# Sheet1.net
KiCad netlist of a schematic drawn in Altium Designer
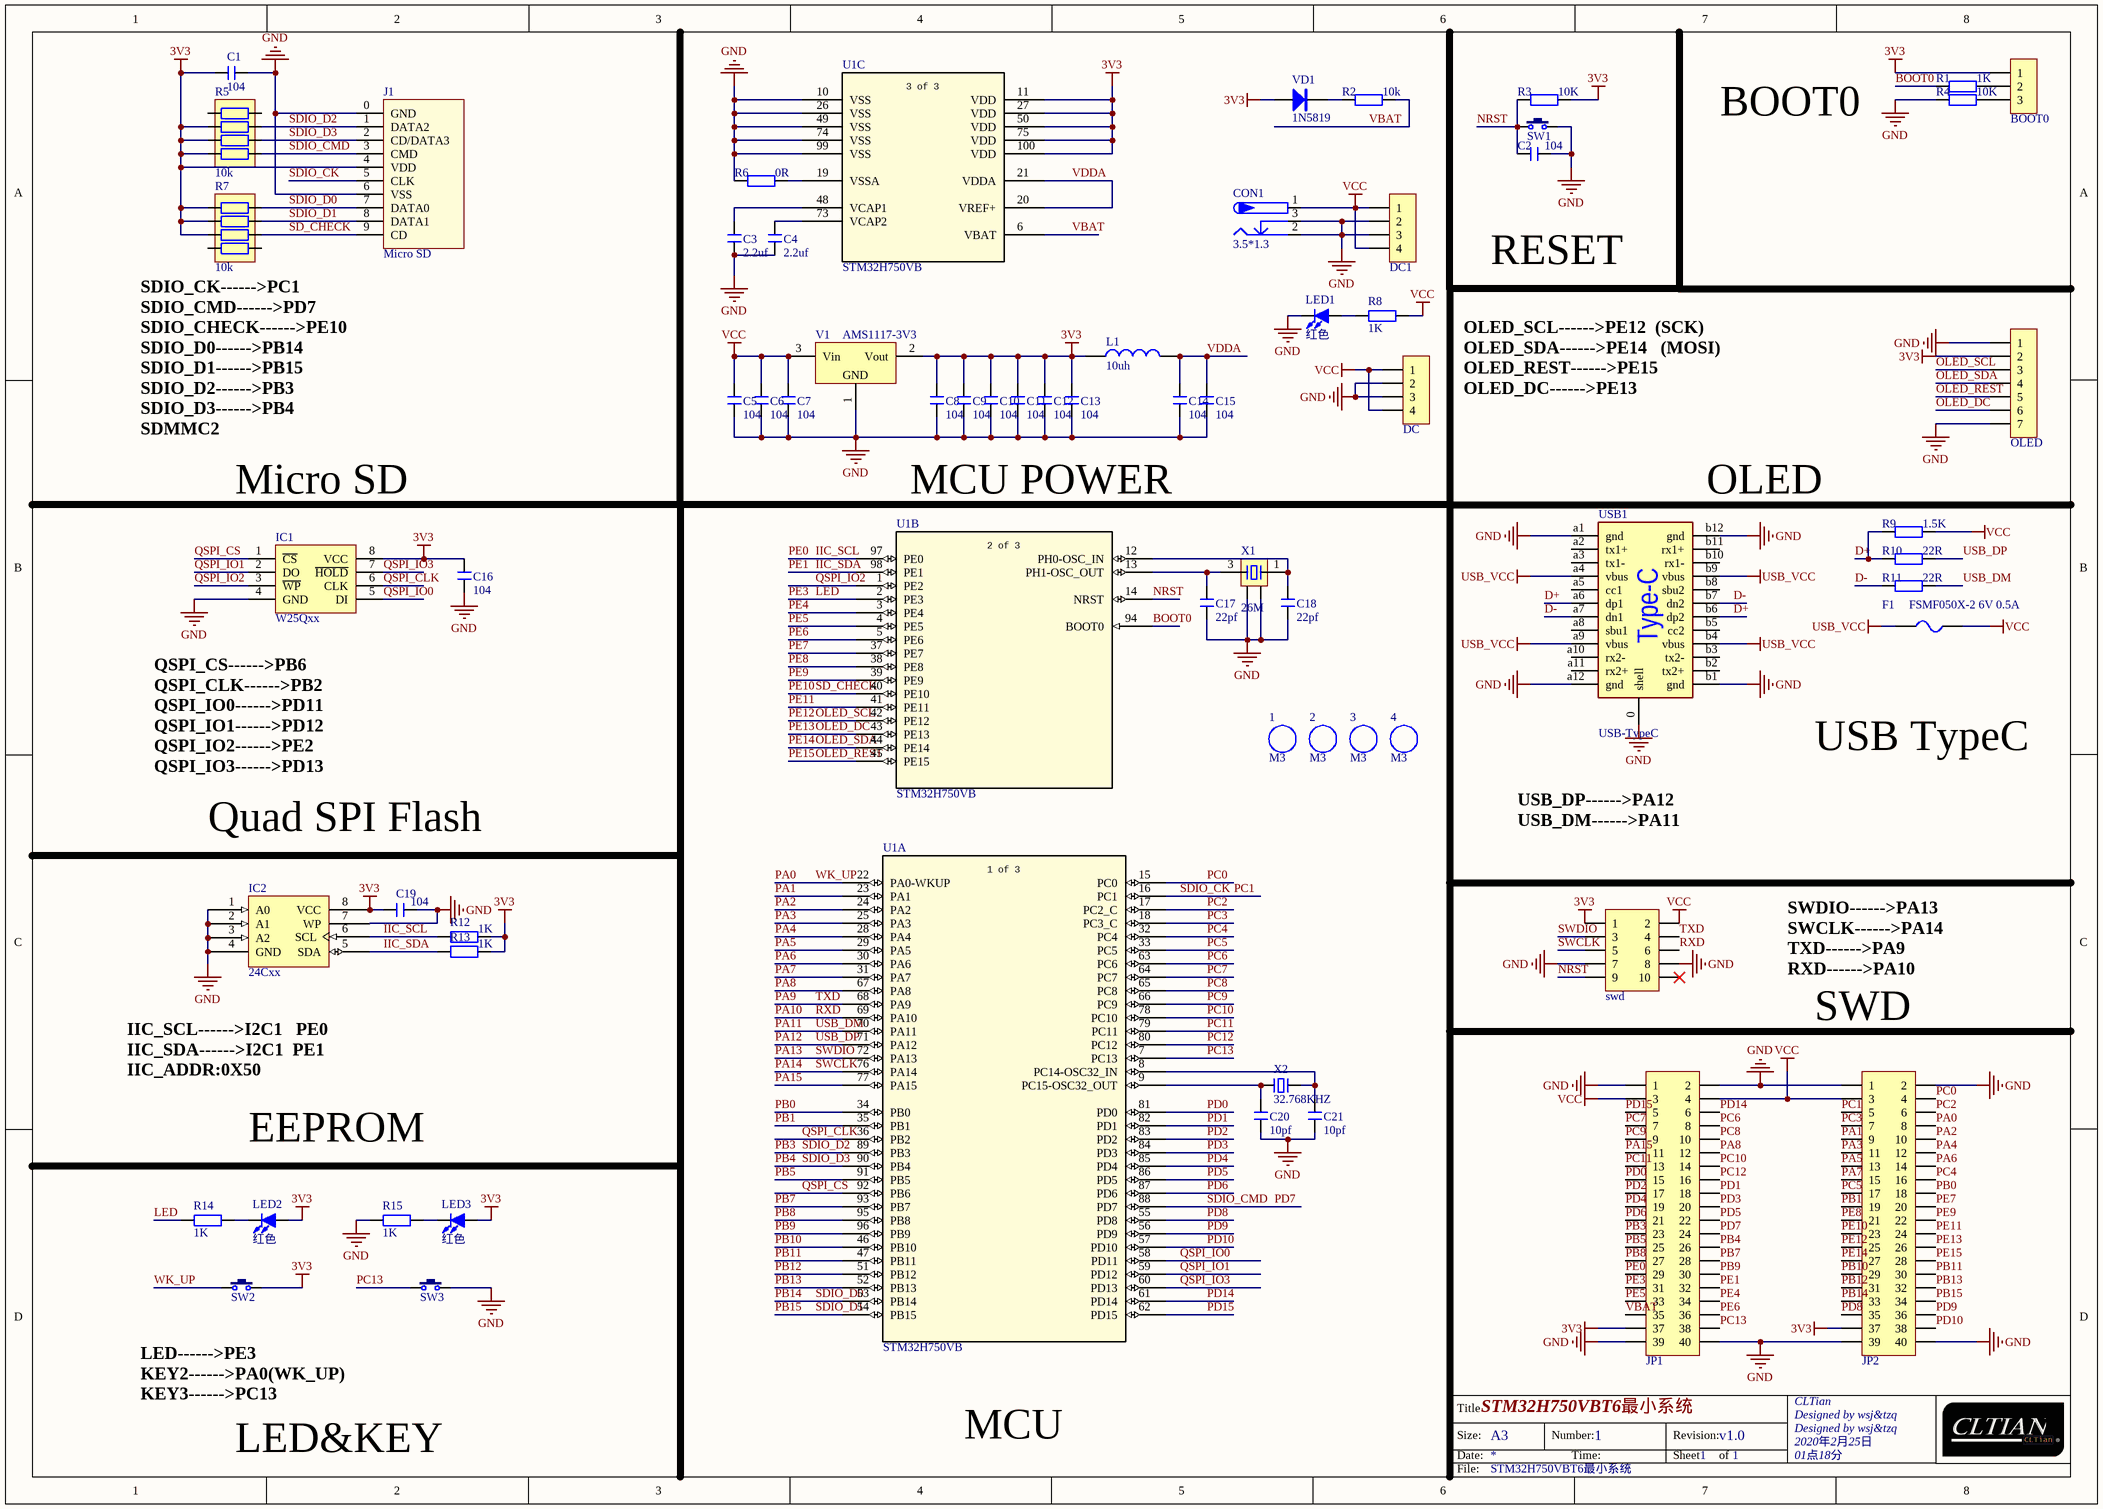
[diagram p0: Sheet1.SchDoc]

(export (version "E")
  (design (tool "Eeschema 10.0.6"))
  (components
    (comp (ref "1")
      (value "M3")
      (footprint "M3 125X200")
      (description "铜柱孔")
      (fields (field (name "版权归属") "黎明电子style"))
      (libsource (lib "未分类器件") (part "M3"))
    )
    (comp (ref "2")
      (value "M3")
      (footprint "M3 125X200")
      (description "铜柱孔")
      (fields (field (name "版权归属") "黎明电子style"))
      (libsource (lib "未分类器件") (part "M3"))
    )
    (comp (ref "3")
      (value "M3")
      (footprint "M3 125X200")
      (description "铜柱孔")
      (fields (field (name "版权归属") "黎明电子style"))
      (libsource (lib "未分类器件") (part "M3"))
    )
    (comp (ref "4")
      (value "M3")
      (footprint "M3 125X200")
      (description "铜柱孔")
      (fields (field (name "版权归属") "黎明电子style"))
      (libsource (lib "未分类器件") (part "M3"))
    )
    (comp (ref "BOOT0")
      (value "HDR-1X3")
      (footprint "HDR-1X3")
      (description "3P接插件")
      (fields (field (name "版权归属") "黎明电子style"))
      (libsource (lib "接插件") (part "Header 3"))
    )
    (comp (ref "C1")
      (value "104")
      (footprint "C 0603")
      (description "无极性贴片电容")
      (fields (field (name "版权归属") "黎明电子style"))
      (libsource (lib "电阻-电容-电感") (part "C"))
    )
    (comp (ref "C2")
      (value "104")
      (footprint "C 0603")
      (description "无极性贴片电容")
      (fields (field (name "版权归属") "黎明电子style"))
      (libsource (lib "电阻-电容-电感") (part "C"))
    )
    (comp (ref "C3")
      (value "2.2uf")
      (footprint "C 0603")
      (description "无极性贴片电容")
      (fields (field (name "版权归属") "黎明电子style"))
      (libsource (lib "电阻-电容-电感") (part "C"))
    )
    (comp (ref "C4")
      (value "2.2uf")
      (footprint "C 0603")
      (description "无极性贴片电容")
      (fields (field (name "版权归属") "黎明电子style"))
      (libsource (lib "电阻-电容-电感") (part "C"))
    )
    (comp (ref "C5")
      (value "104")
      (footprint "C 0603")
      (description "无极性贴片电容")
      (fields (field (name "版权归属") "黎明电子style"))
      (libsource (lib "电阻-电容-电感") (part "C"))
    )
    (comp (ref "C6")
      (value "104")
      (footprint "C 0603")
      (description "无极性贴片电容")
      (fields (field (name "版权归属") "黎明电子style"))
      (libsource (lib "电阻-电容-电感") (part "C"))
    )
    (comp (ref "C7")
      (value "104")
      (footprint "C 0603")
      (description "无极性贴片电容")
      (fields (field (name "版权归属") "黎明电子style"))
      (libsource (lib "电阻-电容-电感") (part "C"))
    )
    (comp (ref "C8")
      (value "104")
      (footprint "C 0603")
      (description "无极性贴片电容")
      (fields (field (name "版权归属") "黎明电子style"))
      (libsource (lib "电阻-电容-电感") (part "C"))
    )
    (comp (ref "C9")
      (value "104")
      (footprint "C 0603")
      (description "无极性贴片电容")
      (fields (field (name "版权归属") "黎明电子style"))
      (libsource (lib "电阻-电容-电感") (part "C"))
    )
    (comp (ref "C10")
      (value "104")
      (footprint "C 0603")
      (description "无极性贴片电容")
      (fields (field (name "版权归属") "黎明电子style"))
      (libsource (lib "电阻-电容-电感") (part "C"))
    )
    (comp (ref "C11")
      (value "104")
      (footprint "C 0603")
      (description "无极性贴片电容")
      (fields (field (name "版权归属") "黎明电子style"))
      (libsource (lib "电阻-电容-电感") (part "C"))
    )
    (comp (ref "C12")
      (value "104")
      (footprint "C 0603")
      (description "无极性贴片电容")
      (fields (field (name "版权归属") "黎明电子style"))
      (libsource (lib "电阻-电容-电感") (part "C"))
    )
    (comp (ref "C13")
      (value "104")
      (footprint "C 0603")
      (description "无极性贴片电容")
      (fields (field (name "版权归属") "黎明电子style"))
      (libsource (lib "电阻-电容-电感") (part "C"))
    )
    (comp (ref "C14")
      (value "104")
      (footprint "C 0603")
      (description "无极性贴片电容")
      (fields (field (name "版权归属") "黎明电子style"))
      (libsource (lib "电阻-电容-电感") (part "C"))
    )
    (comp (ref "C15")
      (value "104")
      (footprint "C 0603")
      (description "无极性贴片电容")
      (fields (field (name "版权归属") "黎明电子style"))
      (libsource (lib "电阻-电容-电感") (part "C"))
    )
    (comp (ref "C16")
      (value "104")
      (footprint "C 0603")
      (description "无极性贴片电容")
      (fields (field (name "版权归属") "黎明电子style"))
      (libsource (lib "电阻-电容-电感") (part "C"))
    )
    (comp (ref "C17")
      (value "22pf")
      (footprint "C 0603")
      (description "无极性贴片电容")
      (fields (field (name "版权归属") "黎明电子style"))
      (libsource (lib "电阻-电容-电感") (part "C"))
    )
    (comp (ref "C18")
      (value "22pf")
      (footprint "C 0603")
      (description "无极性贴片电容")
      (fields (field (name "版权归属") "黎明电子style"))
      (libsource (lib "电阻-电容-电感") (part "C"))
    )
    (comp (ref "C19")
      (value "104")
      (footprint "C 0603")
      (description "无极性贴片电容")
      (fields (field (name "版权归属") "黎明电子style"))
      (libsource (lib "电阻-电容-电感") (part "C"))
    )
    (comp (ref "C20")
      (value "10pf")
      (footprint "C 0603")
      (description "无极性贴片电容")
      (fields (field (name "版权归属") "黎明电子style"))
      (libsource (lib "电阻-电容-电感") (part "C"))
    )
    (comp (ref "C21")
      (value "10pf")
      (footprint "C 0603")
      (description "无极性贴片电容")
      (fields (field (name "版权归属") "黎明电子style"))
      (libsource (lib "电阻-电容-电感") (part "C"))
    )
    (comp (ref "CON1")
      (value "3.5*1.3")
      (footprint "DC-005")
      (description "低压电源接口")
      (fields (field (name "版权归属") "黎明电子style"))
      (libsource (lib "接口类") (part "P-DC"))
    )
    (comp (ref "DC")
      (value "HDR-1X4")
      (footprint "PH2.0 D-W-4P")
      (description "4P接插件")
      (fields (field (name "版权归属") "黎明电子style"))
      (libsource (lib "接插件") (part "Header 4"))
    )
    (comp (ref "DC1")
      (value "HDR-1X4")
      (footprint "PH2.0 D-W-4P")
      (description "4P接插件")
      (fields (field (name "版权归属") "黎明电子style"))
      (libsource (lib "接插件") (part "Header 4"))
    )
    (comp (ref "F1")
      (value "FSMF050X-2 6V 0.5A")
      (footprint "FU 0603")
      (description "贴片保险丝")
      (fields (field (name "版权归属") "黎明电子style"))
      (libsource (lib "保险丝-晶振") (part "FU"))
    )
    (comp (ref "IC1")
      (value "W25Qxx")
      (footprint "SOP8W_N")
      (description "外置Flash")
      (fields (field (name "版权归属") "黎明电子style"))
      (libsource (lib "IC芯片") (part "W25Qxx"))
    )
    (comp (ref "IC2")
      (value "24Cxx")
      (footprint "SOP8_L")
      (description "外置EEPROM")
      (fields (field (name "版权归属") "源创客"))
      (libsource (lib "IC芯片") (part "24Cxx"))
    )
    (comp (ref "J1")
      (value "Micro SD")
      (footprint "Micro SD")
      (description "Micro SD卡")
      (fields (field (name "版权归属") "黎明电子style"))
      (libsource (lib "接口类") (part "Micro SD"))
    )
    (comp (ref "JP1")
      (value "Header 2X11")
      (footprint "HDR-20X2")
      (description "20*2P接插件")
      (fields (field (name "版权归属") "黎明电子style"))
      (libsource (lib "接插件") (part "Header 20X2"))
    )
    (comp (ref "JP2")
      (value "Header 2X11")
      (footprint "HDR-20X2")
      (description "20*2P接插件")
      (fields (field (name "版权归属") "黎明电子style"))
      (libsource (lib "接插件") (part "Header 20X2"))
    )
    (comp (ref "L1")
      (value "10uh")
      (footprint "L 0603")
      (description "小功率贴片电感")
      (fields (field (name "版权归属") "黎明电子style"))
      (libsource (lib "电阻-电容-电感") (part "L"))
    )
    (comp (ref "LED1")
      (value "红色")
      (footprint "LED 0805G")
      (description "贴片LED")
      (fields (field (name "版权归属") "黎明电子style"))
      (libsource (lib "LED") (part "LED-SMD"))
    )
    (comp (ref "LED2")
      (value "红色")
      (footprint "LED 0603B")
      (description "贴片LED")
      (fields (field (name "版权归属") "黎明电子style"))
      (libsource (lib "LED") (part "LED-SMD"))
    )
    (comp (ref "LED3")
      (value "红色")
      (footprint "LED 0603B")
      (description "贴片LED")
      (fields (field (name "版权归属") "黎明电子style"))
      (libsource (lib "LED") (part "LED-SMD"))
    )
    (comp (ref "OLED")
      (value "HDR-1X7")
      (footprint "HDR-1X7")
      (description "7P接插件")
      (fields (field (name "版权归属") "黎明电子style"))
      (libsource (lib "接插件") (part "Header 7"))
    )
    (comp (ref "R1")
      (value "1K")
      (footprint "R 0603-HP")
      (description "贴片电阻")
      (fields (field (name "版权归属") "黎明电子style"))
      (libsource (lib "电阻-电容-电感") (part "R"))
    )
    (comp (ref "R2")
      (value "10k")
      (footprint "R 0603-HP")
      (description "贴片电阻")
      (fields (field (name "版权归属") "黎明电子style"))
      (libsource (lib "电阻-电容-电感") (part "R"))
    )
    (comp (ref "R3")
      (value "10K")
      (footprint "R 0603-HP")
      (description "贴片电阻")
      (fields (field (name "版权归属") "黎明电子style"))
      (libsource (lib "电阻-电容-电感") (part "R"))
    )
    (comp (ref "R4")
      (value "10K")
      (footprint "R 0603-HP")
      (description "贴片电阻")
      (fields (field (name "版权归属") "黎明电子style"))
      (libsource (lib "电阻-电容-电感") (part "R"))
    )
    (comp (ref "R5")
      (value "10k")
      (footprint "RCA-8P4R-0402")
      (description "贴片网络排阻")
      (fields (field (name "版权归属") "黎明电子style"))
      (libsource (lib "电阻-电容-电感") (part "R-8P4R"))
    )
    (comp (ref "R6")
      (value "0R")
      (footprint "R 0603-HP")
      (description "贴片电阻")
      (fields (field (name "版权归属") "黎明电子style"))
      (libsource (lib "电阻-电容-电感") (part "R"))
    )
    (comp (ref "R7")
      (value "10k")
      (footprint "RCA-8P4R-0402")
      (description "贴片网络排阻")
      (fields (field (name "版权归属") "黎明电子style"))
      (libsource (lib "电阻-电容-电感") (part "R-8P4R"))
    )
    (comp (ref "R8")
      (value "1K")
      (footprint "R 0805")
      (description "贴片电阻")
      (fields (field (name "版权归属") "黎明电子style"))
      (libsource (lib "电阻-电容-电感") (part "R"))
    )
    (comp (ref "R9")
      (value "1.5K")
      (footprint "R 0603-HP")
      (description "贴片电阻")
      (fields (field (name "版权归属") "黎明电子style"))
      (libsource (lib "电阻-电容-电感") (part "R"))
    )
    (comp (ref "R10")
      (value "22R")
      (footprint "R 0603-HP")
      (description "贴片电阻")
      (fields (field (name "版权归属") "黎明电子style"))
      (libsource (lib "电阻-电容-电感") (part "R"))
    )
    (comp (ref "R11")
      (value "22R")
      (footprint "R 0603-HP")
      (description "贴片电阻")
      (fields (field (name "版权归属") "黎明电子style"))
      (libsource (lib "电阻-电容-电感") (part "R"))
    )
    (comp (ref "R12")
      (value "1K")
      (footprint "R 0603-HP")
      (description "贴片电阻")
      (fields (field (name "版权归属") "黎明电子style"))
      (libsource (lib "电阻-电容-电感") (part "R"))
    )
    (comp (ref "R13")
      (value "1K")
      (footprint "R 0603-HP")
      (description "贴片电阻")
      (fields (field (name "版权归属") "黎明电子style"))
      (libsource (lib "电阻-电容-电感") (part "R"))
    )
    (comp (ref "R14")
      (value "1K")
      (footprint "R 0603-HP")
      (description "贴片电阻")
      (fields (field (name "版权归属") "黎明电子style"))
      (libsource (lib "电阻-电容-电感") (part "R"))
    )
    (comp (ref "R15")
      (value "1K")
      (footprint "R 0603-HP")
      (description "贴片电阻")
      (fields (field (name "版权归属") "黎明电子style"))
      (libsource (lib "电阻-电容-电感") (part "R"))
    )
    (comp (ref "SW1")
      (value "3x6x5")
      (footprint "TSW SMD-3*6*2.5")
      (description "3x6轻触开关")
      (fields (field (name "版权归属") "黎明电子style"))
      (libsource (lib "按键-开关") (part "TSW 3x6"))
    )
    (comp (ref "SW2")
      (value "3x6x5")
      (footprint "TSW SMD-3*6*2.5")
      (description "3x6轻触开关")
      (fields (field (name "版权归属") "黎明电子style"))
      (libsource (lib "按键-开关") (part "TSW 3x6"))
    )
    (comp (ref "SW3")
      (value "3x6x5")
      (footprint "TSW SMD-3*6*2.5")
      (description "3x6轻触开关")
      (fields (field (name "版权归属") "黎明电子style"))
      (libsource (lib "按键-开关") (part "TSW 3x6"))
    )
    (comp (ref "swd")
      (value "Header 5X2")
      (footprint "HDR-5X2")
      (description "5*2P接插件")
      (fields (field (name "版权归属") "黎明电子style"))
      (libsource (lib "接插件") (part "Header 5X2"))
    )
    (comp (ref "U1")
      (value "STM32H750VB")
      (footprint "LQFP100-14x14mm")
      (description "32位单片机100引脚；")
      (libsource (lib "STM32系列单片机") (part "STM32H750VBTx"))
    )
    (comp (ref "USB1")
      (value "USB-TypeC")
      (footprint "USB_TypeC")
      (description "USB-TypeC型母接口")
      (libsource (lib "接口类") (part "USB_TypeC"))
    )
    (comp (ref "V1")
      (value "AMS1117-3V3")
      (footprint "SOT223_L")
      (description "三端稳压芯片")
      (fields (field (name "版权归属") "黎明电子style"))
      (libsource (lib "IC芯片") (part "AMS1117"))
    )
    (comp (ref "VD1")
      (value "1N5819")
      (footprint "SOD-323")
      (description "高速开关二极管")
      (fields (field (name "版权归属") "黎明电子style"))
      (libsource (lib "二极管-整流桥") (part "1N4148"))
    )
    (comp (ref "X1")
      (value "26M")
      (footprint "XTAL-3225")
      (description "4脚晶振")
      (fields (field (name "版权归属") "黎明电子style"))
      (libsource (lib "保险丝-晶振") (part "XTAL-4"))
    )
    (comp (ref "X2")
      (value "32.768KHZ")
      (footprint "XTAL-3215")
      (description "2脚晶振")
      (fields (field (name "版权归属") "黎明电子style"))
      (libsource (lib "保险丝-晶振") (part "XTAL-2"))
    )
  )
  (nets
    (net (code "1") (name "/BOOT0") (class "Default")
      (node (ref "R1") (pin "1") (pinfunction "1_1") (pintype "passive"))
      (node (ref "U1") (pin "94") (pinfunction "BOOT0_94") (pintype "input"))
    )
    (net (code "2") (name "/D+") (class "Default")
      (node (ref "R10") (pin "1") (pinfunction "1_1") (pintype "passive"))
      (node (ref "R9") (pin "1") (pinfunction "1_1") (pintype "passive"))
      (node (ref "USB1") (pin "a6") (pinfunction "dp1_a6") (pintype "passive"))
      (node (ref "USB1") (pin "b6") (pinfunction "dp2_b6") (pintype "passive"))
    )
    (net (code "3") (name "/D-") (class "Default")
      (node (ref "R11") (pin "1") (pinfunction "1_1") (pintype "passive"))
      (node (ref "USB1") (pin "a7") (pinfunction "dn1_a7") (pintype "passive"))
      (node (ref "USB1") (pin "b7") (pinfunction "dn2_b7") (pintype "passive"))
    )
    (net (code "4") (name "/IIC_SCL") (class "Default")
      (node (ref "IC2") (pin "6") (pinfunction "SCL_6") (pintype "input"))
      (node (ref "JP1") (pin "29") (pinfunction "29_29") (pintype "passive"))
      (node (ref "R12") (pin "1") (pinfunction "1_1") (pintype "passive"))
      (node (ref "U1") (pin "97") (pinfunction "PE0_97") (pintype "bidirectional"))
    )
    (net (code "5") (name "/IIC_SDA") (class "Default")
      (node (ref "IC2") (pin "5") (pinfunction "SDA_5") (pintype "bidirectional"))
      (node (ref "JP1") (pin "32") (pinfunction "32_32") (pintype "passive"))
      (node (ref "R13") (pin "1") (pinfunction "1_1") (pintype "passive"))
      (node (ref "U1") (pin "98") (pinfunction "PE1_98") (pintype "bidirectional"))
    )
    (net (code "6") (name "/LED") (class "Default")
      (node (ref "JP1") (pin "31") (pinfunction "31_31") (pintype "passive"))
      (node (ref "R14") (pin "1") (pinfunction "1_1") (pintype "passive"))
      (node (ref "U1") (pin "2") (pinfunction "PE3_2") (pintype "bidirectional"))
    )
    (net (code "7") (name "/NRST") (class "Default")
      (node (ref "C2") (pin "1") (pinfunction "1_1") (pintype "passive"))
      (node (ref "R3") (pin "2") (pinfunction "2_2") (pintype "passive"))
      (node (ref "SW1") (pin "1") (pinfunction "1_1") (pintype "passive"))
      (node (ref "U1") (pin "14") (pinfunction "NRST_14") (pintype "bidirectional"))
      (node (ref "swd") (pin "9") (pinfunction "9_9") (pintype "passive"))
    )
    (net (code "8") (name "/OLED_DC") (class "Default")
      (node (ref "JP2") (pin "26") (pinfunction "26_26") (pintype "passive"))
      (node (ref "OLED") (pin "6") (pinfunction "6_6") (pintype "passive"))
      (node (ref "U1") (pin "43") (pinfunction "PE13_43") (pintype "bidirectional"))
    )
    (net (code "9") (name "/OLED_REST") (class "Default")
      (node (ref "JP2") (pin "28") (pinfunction "28_28") (pintype "passive"))
      (node (ref "OLED") (pin "5") (pinfunction "5_5") (pintype "passive"))
      (node (ref "U1") (pin "45") (pinfunction "PE15_45") (pintype "bidirectional"))
    )
    (net (code "10") (name "/OLED_SCL") (class "Default")
      (node (ref "JP2") (pin "25") (pinfunction "25_25") (pintype "passive"))
      (node (ref "OLED") (pin "3") (pinfunction "3_3") (pintype "passive"))
      (node (ref "U1") (pin "42") (pinfunction "PE12_42") (pintype "bidirectional"))
    )
    (net (code "11") (name "/OLED_SDA") (class "Default")
      (node (ref "JP2") (pin "27") (pinfunction "27_27") (pintype "passive"))
      (node (ref "OLED") (pin "4") (pinfunction "4_4") (pintype "passive"))
      (node (ref "U1") (pin "44") (pinfunction "PE14_44") (pintype "bidirectional"))
    )
    (net (code "12") (name "/PA0") (class "Default")
      (node (ref "JP2") (pin "8") (pinfunction "8_8") (pintype "passive"))
      (node (ref "SW2") (pin "1") (pinfunction "1_1") (pintype "passive"))
      (node (ref "U1") (pin "22") (pinfunction "PA0-WKUP_22") (pintype "bidirectional"))
    )
    (net (code "13") (name "/PA1") (class "Default")
      (node (ref "JP2") (pin "9") (pinfunction "9_9") (pintype "passive"))
      (node (ref "U1") (pin "23") (pinfunction "PA1_23") (pintype "bidirectional"))
    )
    (net (code "14") (name "/PA2") (class "Default")
      (node (ref "JP2") (pin "10") (pinfunction "10_10") (pintype "passive"))
      (node (ref "U1") (pin "24") (pinfunction "PA2_24") (pintype "bidirectional"))
    )
    (net (code "15") (name "/PA3") (class "Default")
      (node (ref "JP2") (pin "11") (pinfunction "11_11") (pintype "passive"))
      (node (ref "U1") (pin "25") (pinfunction "PA3_25") (pintype "bidirectional"))
    )
    (net (code "16") (name "/PA4") (class "Default")
      (node (ref "JP2") (pin "12") (pinfunction "12_12") (pintype "passive"))
      (node (ref "U1") (pin "28") (pinfunction "PA4_28") (pintype "bidirectional"))
    )
    (net (code "17") (name "/PA5") (class "Default")
      (node (ref "JP2") (pin "13") (pinfunction "13_13") (pintype "passive"))
      (node (ref "U1") (pin "29") (pinfunction "PA5_29") (pintype "bidirectional"))
    )
    (net (code "18") (name "/PA6") (class "Default")
      (node (ref "JP2") (pin "14") (pinfunction "14_14") (pintype "passive"))
      (node (ref "U1") (pin "30") (pinfunction "PA6_30") (pintype "bidirectional"))
    )
    (net (code "19") (name "/PA7") (class "Default")
      (node (ref "JP2") (pin "15") (pinfunction "15_15") (pintype "passive"))
      (node (ref "U1") (pin "31") (pinfunction "PA7_31") (pintype "bidirectional"))
    )
    (net (code "20") (name "/PA8") (class "Default")
      (node (ref "JP1") (pin "12") (pinfunction "12_12") (pintype "passive"))
      (node (ref "U1") (pin "67") (pinfunction "PA8_67") (pintype "bidirectional"))
    )
    (net (code "21") (name "/PA9") (class "Default")
      (node (ref "U1") (pin "68") (pinfunction "PA9_68") (pintype "bidirectional"))
      (node (ref "swd") (pin "4") (pinfunction "4_4") (pintype "passive"))
    )
    (net (code "22") (name "/PA10") (class "Default")
      (node (ref "U1") (pin "69") (pinfunction "PA10_69") (pintype "bidirectional"))
      (node (ref "swd") (pin "6") (pinfunction "6_6") (pintype "passive"))
    )
    (net (code "23") (name "/PA11") (class "Default")
      (node (ref "R11") (pin "2") (pinfunction "2_2") (pintype "passive"))
      (node (ref "U1") (pin "70") (pinfunction "PA11_70") (pintype "bidirectional"))
    )
    (net (code "24") (name "/PA12") (class "Default")
      (node (ref "R10") (pin "2") (pinfunction "2_2") (pintype "passive"))
      (node (ref "U1") (pin "71") (pinfunction "PA12_71") (pintype "bidirectional"))
    )
    (net (code "25") (name "/PA13") (class "Default")
      (node (ref "U1") (pin "72") (pinfunction "PA13_72") (pintype "bidirectional"))
      (node (ref "swd") (pin "3") (pinfunction "3_3") (pintype "passive"))
    )
    (net (code "26") (name "/PA14") (class "Default")
      (node (ref "U1") (pin "76") (pinfunction "PA14_76") (pintype "bidirectional"))
      (node (ref "swd") (pin "5") (pinfunction "5_5") (pintype "passive"))
    )
    (net (code "27") (name "/PA15") (class "Default")
      (node (ref "JP1") (pin "11") (pinfunction "11_11") (pintype "passive"))
      (node (ref "U1") (pin "77") (pinfunction "PA15_77") (pintype "bidirectional"))
    )
    (net (code "28") (name "/PB0") (class "Default")
      (node (ref "JP2") (pin "18") (pinfunction "18_18") (pintype "passive"))
      (node (ref "U1") (pin "34") (pinfunction "PB0_34") (pintype "bidirectional"))
    )
    (net (code "29") (name "/PB1") (class "Default")
      (node (ref "JP2") (pin "19") (pinfunction "19_19") (pintype "passive"))
      (node (ref "U1") (pin "35") (pinfunction "PB1_35") (pintype "bidirectional"))
    )
    (net (code "30") (name "/PB3") (class "Default")
      (node (ref "J1") (pin "1") (pinfunction "DATA2_1") (pintype "passive"))
      (node (ref "JP1") (pin "23") (pinfunction "23_23") (pintype "passive"))
      (node (ref "R5") (pin "7") (pinfunction "7_7") (pintype "passive"))
      (node (ref "U1") (pin "89") (pinfunction "PB3_89") (pintype "bidirectional"))
    )
    (net (code "31") (name "/PB4") (class "Default")
      (node (ref "J1") (pin "2") (pinfunction "CD/DATA3_2") (pintype "passive"))
      (node (ref "JP1") (pin "26") (pinfunction "26_26") (pintype "passive"))
      (node (ref "R5") (pin "6") (pinfunction "6_6") (pintype "passive"))
      (node (ref "U1") (pin "90") (pinfunction "PB4_90") (pintype "bidirectional"))
    )
    (net (code "32") (name "/PB5") (class "Default")
      (node (ref "JP1") (pin "25") (pinfunction "25_25") (pintype "passive"))
      (node (ref "U1") (pin "91") (pinfunction "PB5_91") (pintype "bidirectional"))
    )
    (net (code "33") (name "/PB7") (class "Default")
      (node (ref "JP1") (pin "28") (pinfunction "28_28") (pintype "passive"))
      (node (ref "U1") (pin "93") (pinfunction "PB7_93") (pintype "bidirectional"))
    )
    (net (code "34") (name "/PB8") (class "Default")
      (node (ref "JP1") (pin "27") (pinfunction "27_27") (pintype "passive"))
      (node (ref "U1") (pin "95") (pinfunction "PB8_95") (pintype "bidirectional"))
    )
    (net (code "35") (name "/PB9") (class "Default")
      (node (ref "JP1") (pin "30") (pinfunction "30_30") (pintype "passive"))
      (node (ref "U1") (pin "96") (pinfunction "PB9_96") (pintype "bidirectional"))
    )
    (net (code "36") (name "/PB10") (class "Default")
      (node (ref "JP2") (pin "29") (pinfunction "29_29") (pintype "passive"))
      (node (ref "U1") (pin "46") (pinfunction "PB10_46") (pintype "bidirectional"))
    )
    (net (code "37") (name "/PB11") (class "Default")
      (node (ref "JP2") (pin "30") (pinfunction "30_30") (pintype "passive"))
      (node (ref "U1") (pin "47") (pinfunction "PB11_47") (pintype "bidirectional"))
    )
    (net (code "38") (name "/PB12") (class "Default")
      (node (ref "JP2") (pin "31") (pinfunction "31_31") (pintype "passive"))
      (node (ref "U1") (pin "51") (pinfunction "PB12_51") (pintype "bidirectional"))
    )
    (net (code "39") (name "/PB13") (class "Default")
      (node (ref "JP2") (pin "32") (pinfunction "32_32") (pintype "passive"))
      (node (ref "U1") (pin "52") (pinfunction "PB13_52") (pintype "bidirectional"))
    )
    (net (code "40") (name "/PB14") (class "Default")
      (node (ref "J1") (pin "7") (pinfunction "DATA0_7") (pintype "passive"))
      (node (ref "JP2") (pin "33") (pinfunction "33_33") (pintype "passive"))
      (node (ref "R7") (pin "8") (pinfunction "8_8") (pintype "passive"))
      (node (ref "U1") (pin "53") (pinfunction "PB14_53") (pintype "bidirectional"))
    )
    (net (code "41") (name "/PB15") (class "Default")
      (node (ref "J1") (pin "8") (pinfunction "DATA1_8") (pintype "passive"))
      (node (ref "JP2") (pin "34") (pinfunction "34_34") (pintype "passive"))
      (node (ref "R7") (pin "7") (pinfunction "7_7") (pintype "passive"))
      (node (ref "U1") (pin "54") (pinfunction "PB15_54") (pintype "bidirectional"))
    )
    (net (code "42") (name "/PC0") (class "Default")
      (node (ref "JP2") (pin "4") (pinfunction "4_4") (pintype "passive"))
      (node (ref "U1") (pin "15") (pinfunction "PC0_15") (pintype "bidirectional"))
    )
    (net (code "43") (name "/PC1") (class "Default")
      (node (ref "J1") (pin "5") (pinfunction "CLK_5") (pintype "passive"))
      (node (ref "JP2") (pin "5") (pinfunction "5_5") (pintype "passive"))
      (node (ref "U1") (pin "16") (pinfunction "PC1_16") (pintype "bidirectional"))
    )
    (net (code "44") (name "/PC2") (class "Default")
      (node (ref "JP2") (pin "6") (pinfunction "6_6") (pintype "passive"))
      (node (ref "U1") (pin "17") (pinfunction "PC2_C_17") (pintype "bidirectional"))
    )
    (net (code "45") (name "/PC3") (class "Default")
      (node (ref "JP2") (pin "7") (pinfunction "7_7") (pintype "passive"))
      (node (ref "U1") (pin "18") (pinfunction "PC3_C_18") (pintype "bidirectional"))
    )
    (net (code "46") (name "/PC4") (class "Default")
      (node (ref "JP2") (pin "16") (pinfunction "16_16") (pintype "passive"))
      (node (ref "U1") (pin "32") (pinfunction "PC4_32") (pintype "bidirectional"))
    )
    (net (code "47") (name "/PC5") (class "Default")
      (node (ref "JP2") (pin "17") (pinfunction "17_17") (pintype "passive"))
      (node (ref "U1") (pin "33") (pinfunction "PC5_33") (pintype "bidirectional"))
    )
    (net (code "48") (name "/PC6") (class "Default")
      (node (ref "JP1") (pin "8") (pinfunction "8_8") (pintype "passive"))
      (node (ref "U1") (pin "63") (pinfunction "PC6_63") (pintype "bidirectional"))
    )
    (net (code "49") (name "/PC7") (class "Default")
      (node (ref "JP1") (pin "7") (pinfunction "7_7") (pintype "passive"))
      (node (ref "U1") (pin "64") (pinfunction "PC7_64") (pintype "bidirectional"))
    )
    (net (code "50") (name "/PC8") (class "Default")
      (node (ref "JP1") (pin "10") (pinfunction "10_10") (pintype "passive"))
      (node (ref "U1") (pin "65") (pinfunction "PC8_65") (pintype "bidirectional"))
    )
    (net (code "51") (name "/PC9") (class "Default")
      (node (ref "JP1") (pin "9") (pinfunction "9_9") (pintype "passive"))
      (node (ref "U1") (pin "66") (pinfunction "PC9_66") (pintype "bidirectional"))
    )
    (net (code "52") (name "/PC10") (class "Default")
      (node (ref "JP1") (pin "14") (pinfunction "14_14") (pintype "passive"))
      (node (ref "U1") (pin "78") (pinfunction "PC10_78") (pintype "bidirectional"))
    )
    (net (code "53") (name "/PC11") (class "Default")
      (node (ref "JP1") (pin "13") (pinfunction "13_13") (pintype "passive"))
      (node (ref "U1") (pin "79") (pinfunction "PC11_79") (pintype "bidirectional"))
    )
    (net (code "54") (name "/PC12") (class "Default")
      (node (ref "JP1") (pin "16") (pinfunction "16_16") (pintype "passive"))
      (node (ref "U1") (pin "80") (pinfunction "PC12_80") (pintype "bidirectional"))
    )
    (net (code "55") (name "/PC13") (class "Default")
      (node (ref "JP1") (pin "38") (pinfunction "38_38") (pintype "passive"))
      (node (ref "SW3") (pin "1") (pinfunction "1_1") (pintype "passive"))
      (node (ref "U1") (pin "7") (pinfunction "PC13_7") (pintype "bidirectional"))
    )
    (net (code "56") (name "/PD0") (class "Default")
      (node (ref "JP1") (pin "15") (pinfunction "15_15") (pintype "passive"))
      (node (ref "U1") (pin "81") (pinfunction "PD0_81") (pintype "bidirectional"))
    )
    (net (code "57") (name "/PD1") (class "Default")
      (node (ref "JP1") (pin "18") (pinfunction "18_18") (pintype "passive"))
      (node (ref "U1") (pin "82") (pinfunction "PD1_82") (pintype "bidirectional"))
    )
    (net (code "58") (name "/PD2") (class "Default")
      (node (ref "JP1") (pin "17") (pinfunction "17_17") (pintype "passive"))
      (node (ref "U1") (pin "83") (pinfunction "PD2_83") (pintype "bidirectional"))
    )
    (net (code "59") (name "/PD3") (class "Default")
      (node (ref "JP1") (pin "20") (pinfunction "20_20") (pintype "passive"))
      (node (ref "U1") (pin "84") (pinfunction "PD3_84") (pintype "bidirectional"))
    )
    (net (code "60") (name "/PD4") (class "Default")
      (node (ref "JP1") (pin "19") (pinfunction "19_19") (pintype "passive"))
      (node (ref "U1") (pin "85") (pinfunction "PD4_85") (pintype "bidirectional"))
    )
    (net (code "61") (name "/PD5") (class "Default")
      (node (ref "JP1") (pin "22") (pinfunction "22_22") (pintype "passive"))
      (node (ref "U1") (pin "86") (pinfunction "PD5_86") (pintype "bidirectional"))
    )
    (net (code "62") (name "/PD6") (class "Default")
      (node (ref "JP1") (pin "21") (pinfunction "21_21") (pintype "passive"))
      (node (ref "U1") (pin "87") (pinfunction "PD6_87") (pintype "bidirectional"))
    )
    (net (code "63") (name "/PD7") (class "Default")
      (node (ref "J1") (pin "3") (pinfunction "CMD_3") (pintype "passive"))
      (node (ref "JP1") (pin "24") (pinfunction "24_24") (pintype "passive"))
      (node (ref "R5") (pin "5") (pinfunction "5_5") (pintype "passive"))
      (node (ref "U1") (pin "88") (pinfunction "PD7_88") (pintype "bidirectional"))
    )
    (net (code "64") (name "/PD8") (class "Default")
      (node (ref "JP2") (pin "35") (pinfunction "35_35") (pintype "passive"))
      (node (ref "U1") (pin "55") (pinfunction "PD8_55") (pintype "bidirectional"))
    )
    (net (code "65") (name "/PD9") (class "Default")
      (node (ref "JP2") (pin "36") (pinfunction "36_36") (pintype "passive"))
      (node (ref "U1") (pin "56") (pinfunction "PD9_56") (pintype "bidirectional"))
    )
    (net (code "66") (name "/PD10") (class "Default")
      (node (ref "JP2") (pin "38") (pinfunction "38_38") (pintype "passive"))
      (node (ref "U1") (pin "57") (pinfunction "PD10_57") (pintype "bidirectional"))
    )
    (net (code "67") (name "/PD14") (class "Default")
      (node (ref "JP1") (pin "6") (pinfunction "6_6") (pintype "passive"))
      (node (ref "U1") (pin "61") (pinfunction "PD14_61") (pintype "bidirectional"))
    )
    (net (code "68") (name "/PD15") (class "Default")
      (node (ref "JP1") (pin "5") (pinfunction "5_5") (pintype "passive"))
      (node (ref "U1") (pin "62") (pinfunction "PD15_62") (pintype "bidirectional"))
    )
    (net (code "69") (name "/PE4") (class "Default")
      (node (ref "JP1") (pin "34") (pinfunction "34_34") (pintype "passive"))
      (node (ref "U1") (pin "3") (pinfunction "PE4_3") (pintype "bidirectional"))
    )
    (net (code "70") (name "/PE5") (class "Default")
      (node (ref "JP1") (pin "33") (pinfunction "33_33") (pintype "passive"))
      (node (ref "U1") (pin "4") (pinfunction "PE5_4") (pintype "bidirectional"))
    )
    (net (code "71") (name "/PE6") (class "Default")
      (node (ref "JP1") (pin "36") (pinfunction "36_36") (pintype "passive"))
      (node (ref "U1") (pin "5") (pinfunction "PE6_5") (pintype "bidirectional"))
    )
    (net (code "72") (name "/PE7") (class "Default")
      (node (ref "JP2") (pin "20") (pinfunction "20_20") (pintype "passive"))
      (node (ref "U1") (pin "37") (pinfunction "PE7_37") (pintype "bidirectional"))
    )
    (net (code "73") (name "/PE8") (class "Default")
      (node (ref "JP2") (pin "21") (pinfunction "21_21") (pintype "passive"))
      (node (ref "U1") (pin "38") (pinfunction "PE8_38") (pintype "bidirectional"))
    )
    (net (code "74") (name "/PE9") (class "Default")
      (node (ref "JP2") (pin "22") (pinfunction "22_22") (pintype "passive"))
      (node (ref "U1") (pin "39") (pinfunction "PE9_39") (pintype "bidirectional"))
    )
    (net (code "75") (name "/PE10") (class "Default")
      (node (ref "J1") (pin "9") (pinfunction "CD_9") (pintype "passive"))
      (node (ref "JP2") (pin "23") (pinfunction "23_23") (pintype "passive"))
      (node (ref "R7") (pin "6") (pinfunction "6_6") (pintype "passive"))
      (node (ref "U1") (pin "40") (pinfunction "PE10_40") (pintype "bidirectional"))
    )
    (net (code "76") (name "/PE11") (class "Default")
      (node (ref "JP2") (pin "24") (pinfunction "24_24") (pintype "passive"))
      (node (ref "U1") (pin "41") (pinfunction "PE11_41") (pintype "bidirectional"))
    )
    (net (code "77") (name "/QSPI_CLK") (class "Default")
      (node (ref "IC1") (pin "6") (pinfunction "CLK_6") (pintype "passive"))
      (node (ref "U1") (pin "36") (pinfunction "PB2_36") (pintype "bidirectional"))
    )
    (net (code "78") (name "/QSPI_CS") (class "Default")
      (node (ref "IC1") (pin "1") (pinfunction "~{CS}_1") (pintype "passive"))
      (node (ref "U1") (pin "92") (pinfunction "PB6_92") (pintype "bidirectional"))
    )
    (net (code "79") (name "/QSPI_IO0") (class "Default")
      (node (ref "IC1") (pin "5") (pinfunction "DI_5") (pintype "passive"))
      (node (ref "U1") (pin "58") (pinfunction "PD11_58") (pintype "bidirectional"))
    )
    (net (code "80") (name "/QSPI_IO1") (class "Default")
      (node (ref "IC1") (pin "2") (pinfunction "DO_2") (pintype "passive"))
      (node (ref "U1") (pin "59") (pinfunction "PD12_59") (pintype "bidirectional"))
    )
    (net (code "81") (name "/QSPI_IO2") (class "Default")
      (node (ref "IC1") (pin "3") (pinfunction "~{WP}_3") (pintype "passive"))
      (node (ref "U1") (pin "1") (pinfunction "PE2_1") (pintype "bidirectional"))
    )
    (net (code "82") (name "/QSPI_IO3") (class "Default")
      (node (ref "IC1") (pin "7") (pinfunction "~{HOLD}_7") (pintype "passive"))
      (node (ref "U1") (pin "60") (pinfunction "PD13_60") (pintype "bidirectional"))
    )
    (net (code "83") (name "/VBAT") (class "Default")
      (node (ref "JP1") (pin "35") (pinfunction "35_35") (pintype "passive"))
      (node (ref "R2") (pin "1") (pinfunction "1_1") (pintype "passive"))
      (node (ref "U1") (pin "6") (pinfunction "VBAT_6") (pintype "power_in"))
    )
    (net (code "84") (name "/VDDA") (class "Default")
      (node (ref "C14") (pin "2") (pinfunction "2_2") (pintype "passive"))
      (node (ref "C15") (pin "2") (pinfunction "2_2") (pintype "passive"))
      (node (ref "L1") (pin "2") (pinfunction "2_2") (pintype "passive"))
      (node (ref "U1") (pin "20") (pinfunction "VREF+_20") (pintype "power_in"))
      (node (ref "U1") (pin "21") (pinfunction "VDDA_21") (pintype "power_in"))
    )
    (net (code "85") (name "3V3") (class "Default")
      (node (ref "BOOT0") (pin "1") (pinfunction "1_1") (pintype "passive"))
      (node (ref "C1") (pin "2") (pinfunction "2_2") (pintype "passive"))
      (node (ref "C10") (pin "2") (pinfunction "2_2") (pintype "passive"))
      (node (ref "C11") (pin "2") (pinfunction "2_2") (pintype "passive"))
      (node (ref "C12") (pin "2") (pinfunction "2_2") (pintype "passive"))
      (node (ref "C13") (pin "2") (pinfunction "2_2") (pintype "passive"))
      (node (ref "C16") (pin "2") (pinfunction "2_2") (pintype "passive"))
      (node (ref "C19") (pin "2") (pinfunction "2_2") (pintype "passive"))
      (node (ref "C8") (pin "2") (pinfunction "2_2") (pintype "passive"))
      (node (ref "C9") (pin "2") (pinfunction "2_2") (pintype "passive"))
      (node (ref "IC1") (pin "8") (pinfunction "VCC_8") (pintype "passive"))
      (node (ref "IC2") (pin "8") (pinfunction "VCC_8") (pintype "power_in"))
      (node (ref "J1") (pin "4") (pinfunction "VDD_4") (pintype "passive"))
      (node (ref "JP1") (pin "37") (pinfunction "37_37") (pintype "passive"))
      (node (ref "JP2") (pin "37") (pinfunction "37_37") (pintype "passive"))
      (node (ref "L1") (pin "1") (pinfunction "1_1") (pintype "passive"))
      (node (ref "LED2") (pin "1") (pinfunction "A_1") (pintype "passive"))
      (node (ref "LED3") (pin "1") (pinfunction "A_1") (pintype "passive"))
      (node (ref "OLED") (pin "2") (pinfunction "2_2") (pintype "passive"))
      (node (ref "R12") (pin "2") (pinfunction "2_2") (pintype "passive"))
      (node (ref "R13") (pin "2") (pinfunction "2_2") (pintype "passive"))
      (node (ref "R3") (pin "1") (pinfunction "1_1") (pintype "passive"))
      (node (ref "R5") (pin "2") (pinfunction "2_2") (pintype "passive"))
      (node (ref "R5") (pin "3") (pinfunction "3_3") (pintype "passive"))
      (node (ref "R5") (pin "4") (pinfunction "4_4") (pintype "passive"))
      (node (ref "R7") (pin "1") (pinfunction "1_1") (pintype "passive"))
      (node (ref "R7") (pin "2") (pinfunction "2_2") (pintype "passive"))
      (node (ref "R7") (pin "3") (pinfunction "3_3") (pintype "passive"))
      (node (ref "SW2") (pin "2") (pinfunction "2_2") (pintype "passive"))
      (node (ref "U1") (pin "100") (pinfunction "VDD_100") (pintype "power_in"))
      (node (ref "U1") (pin "11") (pinfunction "VDD_11") (pintype "power_in"))
      (node (ref "U1") (pin "27") (pinfunction "VDD_27") (pintype "power_in"))
      (node (ref "U1") (pin "50") (pinfunction "VDD_50") (pintype "power_in"))
      (node (ref "U1") (pin "75") (pinfunction "VDD_75") (pintype "power_in"))
      (node (ref "V1") (pin "2") (pinfunction "Vout_2") (pintype "passive"))
      (node (ref "VD1") (pin "1") (pinfunction "A_1") (pintype "passive"))
      (node (ref "swd") (pin "1") (pinfunction "1_1") (pintype "passive"))
    )
    (net (code "86") (name "GND") (class "Default")
      (node (ref "C1") (pin "1") (pinfunction "1_1") (pintype "passive"))
      (node (ref "C10") (pin "1") (pinfunction "1_1") (pintype "passive"))
      (node (ref "C11") (pin "1") (pinfunction "1_1") (pintype "passive"))
      (node (ref "C12") (pin "1") (pinfunction "1_1") (pintype "passive"))
      (node (ref "C13") (pin "1") (pinfunction "1_1") (pintype "passive"))
      (node (ref "C14") (pin "1") (pinfunction "1_1") (pintype "passive"))
      (node (ref "C15") (pin "1") (pinfunction "1_1") (pintype "passive"))
      (node (ref "C16") (pin "1") (pinfunction "1_1") (pintype "passive"))
      (node (ref "C17") (pin "1") (pinfunction "1_1") (pintype "passive"))
      (node (ref "C18") (pin "1") (pinfunction "1_1") (pintype "passive"))
      (node (ref "C19") (pin "1") (pinfunction "1_1") (pintype "passive"))
      (node (ref "C2") (pin "2") (pinfunction "2_2") (pintype "passive"))
      (node (ref "C20") (pin "1") (pinfunction "1_1") (pintype "passive"))
      (node (ref "C21") (pin "1") (pinfunction "1_1") (pintype "passive"))
      (node (ref "C3") (pin "1") (pinfunction "1_1") (pintype "passive"))
      (node (ref "C4") (pin "1") (pinfunction "1_1") (pintype "passive"))
      (node (ref "C5") (pin "1") (pinfunction "1_1") (pintype "passive"))
      (node (ref "C6") (pin "1") (pinfunction "1_1") (pintype "passive"))
      (node (ref "C7") (pin "1") (pinfunction "1_1") (pintype "passive"))
      (node (ref "C8") (pin "1") (pinfunction "1_1") (pintype "passive"))
      (node (ref "C9") (pin "1") (pinfunction "1_1") (pintype "passive"))
      (node (ref "CON1") (pin "2") (pintype "power_in"))
      (node (ref "CON1") (pin "3") (pintype "power_in"))
      (node (ref "DC") (pin "2") (pinfunction "2_2") (pintype "passive"))
      (node (ref "DC") (pin "3") (pinfunction "3_3") (pintype "passive"))
      (node (ref "DC1") (pin "2") (pinfunction "2_2") (pintype "passive"))
      (node (ref "DC1") (pin "3") (pinfunction "3_3") (pintype "passive"))
      (node (ref "IC1") (pin "4") (pinfunction "GND_4") (pintype "passive"))
      (node (ref "IC2") (pin "1") (pinfunction "A0_1") (pintype "input"))
      (node (ref "IC2") (pin "2") (pinfunction "A1_2") (pintype "input"))
      (node (ref "IC2") (pin "3") (pinfunction "A2_3") (pintype "input"))
      (node (ref "IC2") (pin "4") (pinfunction "GND_4") (pintype "passive"))
      (node (ref "IC2") (pin "7") (pinfunction "WP_7") (pintype "passive"))
      (node (ref "J1") (pin "0") (pinfunction "GND_0") (pintype "passive"))
      (node (ref "J1") (pin "6") (pinfunction "VSS_6") (pintype "passive"))
      (node (ref "JP1") (pin "1") (pinfunction "1_1") (pintype "passive"))
      (node (ref "JP1") (pin "2") (pinfunction "2_2") (pintype "passive"))
      (node (ref "JP1") (pin "39") (pinfunction "39_39") (pintype "passive"))
      (node (ref "JP1") (pin "40") (pinfunction "40_40") (pintype "passive"))
      (node (ref "JP2") (pin "1") (pinfunction "1_1") (pintype "passive"))
      (node (ref "JP2") (pin "2") (pinfunction "2_2") (pintype "passive"))
      (node (ref "JP2") (pin "39") (pinfunction "39_39") (pintype "passive"))
      (node (ref "JP2") (pin "40") (pinfunction "40_40") (pintype "passive"))
      (node (ref "LED1") (pin "2") (pinfunction "K_2") (pintype "passive"))
      (node (ref "OLED") (pin "1") (pinfunction "1_1") (pintype "passive"))
      (node (ref "OLED") (pin "7") (pinfunction "7_7") (pintype "passive"))
      (node (ref "R15") (pin "1") (pinfunction "1_1") (pintype "passive"))
      (node (ref "R4") (pin "1") (pinfunction "1_1") (pintype "passive"))
      (node (ref "R6") (pin "2") (pinfunction "2_2") (pintype "passive"))
      (node (ref "SW1") (pin "2") (pinfunction "2_2") (pintype "passive"))
      (node (ref "SW3") (pin "2") (pinfunction "2_2") (pintype "passive"))
      (node (ref "U1") (pin "10") (pinfunction "VSS_10") (pintype "power_in"))
      (node (ref "U1") (pin "26") (pinfunction "VSS_26") (pintype "power_in"))
      (node (ref "U1") (pin "49") (pinfunction "VSS_49") (pintype "power_in"))
      (node (ref "U1") (pin "74") (pinfunction "VSS_74") (pintype "power_in"))
      (node (ref "U1") (pin "99") (pinfunction "VSS_99") (pintype "power_in"))
      (node (ref "USB1") (pin "0") (pinfunction "shell_0") (pintype "passive"))
      (node (ref "USB1") (pin "a1") (pinfunction "gnd_a1") (pintype "passive"))
      (node (ref "USB1") (pin "a12") (pinfunction "gnd_a12") (pintype "passive"))
      (node (ref "USB1") (pin "b1") (pinfunction "gnd_b1") (pintype "passive"))
      (node (ref "USB1") (pin "b12") (pinfunction "gnd_b12") (pintype "passive"))
      (node (ref "V1") (pin "1") (pinfunction "GND_1") (pintype "passive"))
      (node (ref "X1") (pin "2") (pinfunction "2_2") (pintype "passive"))
      (node (ref "X1") (pin "4") (pinfunction "4_4") (pintype "passive"))
      (node (ref "swd") (pin "7") (pinfunction "7_7") (pintype "passive"))
      (node (ref "swd") (pin "8") (pinfunction "8_8") (pintype "passive"))
    )
    (net (code "87") (name "Net-(BOOT0-Pad2)") (class "Default")
      (node (ref "BOOT0") (pin "2") (pinfunction "2_2") (pintype "passive"))
      (node (ref "R1") (pin "2") (pinfunction "2_2") (pintype "passive"))
    )
    (net (code "88") (name "Net-(BOOT0-Pad3)") (class "Default")
      (node (ref "BOOT0") (pin "3") (pinfunction "3_3") (pintype "passive"))
      (node (ref "R4") (pin "2") (pinfunction "2_2") (pintype "passive"))
    )
    (net (code "89") (name "Net-(LED1-A)") (class "Default")
      (node (ref "LED1") (pin "1") (pinfunction "A_1") (pintype "passive"))
      (node (ref "R8") (pin "1") (pinfunction "1_1") (pintype "passive"))
    )
    (net (code "90") (name "Net-(LED2-K)") (class "Default")
      (node (ref "LED2") (pin "2") (pinfunction "K_2") (pintype "passive"))
      (node (ref "R14") (pin "2") (pinfunction "2_2") (pintype "passive"))
    )
    (net (code "91") (name "Net-(LED3-K)") (class "Default")
      (node (ref "LED3") (pin "2") (pinfunction "K_2") (pintype "passive"))
      (node (ref "R15") (pin "2") (pinfunction "2_2") (pintype "passive"))
    )
    (net (code "92") (name "Net-(U1A-PC14-OSC32_IN)") (class "Default")
      (node (ref "C21") (pin "2") (pinfunction "2_2") (pintype "passive"))
      (node (ref "U1") (pin "8") (pinfunction "PC14-OSC32_IN_8") (pintype "bidirectional"))
      (node (ref "X2") (pin "2") (pinfunction "2_2") (pintype "passive"))
    )
    (net (code "93") (name "Net-(U1A-PC15-OSC32_OUT)") (class "Default")
      (node (ref "C20") (pin "2") (pinfunction "2_2") (pintype "passive"))
      (node (ref "U1") (pin "9") (pinfunction "PC15-OSC32_OUT_9") (pintype "bidirectional"))
      (node (ref "X2") (pin "1") (pinfunction "1_1") (pintype "passive"))
    )
    (net (code "94") (name "Net-(U1B-PH0-OSC_IN)") (class "Default")
      (node (ref "C18") (pin "2") (pinfunction "2_2") (pintype "passive"))
      (node (ref "U1") (pin "12") (pinfunction "PH0-OSC_IN_12") (pintype "bidirectional"))
      (node (ref "X1") (pin "1") (pinfunction "1_1") (pintype "passive"))
    )
    (net (code "95") (name "Net-(U1B-PH1-OSC_OUT)") (class "Default")
      (node (ref "C17") (pin "2") (pinfunction "2_2") (pintype "passive"))
      (node (ref "U1") (pin "13") (pinfunction "PH1-OSC_OUT_13") (pintype "bidirectional"))
      (node (ref "X1") (pin "3") (pinfunction "3_3") (pintype "passive"))
    )
    (net (code "96") (name "Net-(U1C-VCAP1)") (class "Default")
      (node (ref "C3") (pin "2") (pinfunction "2_2") (pintype "passive"))
      (node (ref "U1") (pin "48") (pinfunction "VCAP1_48") (pintype "power_in"))
    )
    (net (code "97") (name "Net-(U1C-VCAP2)") (class "Default")
      (node (ref "C4") (pin "2") (pinfunction "2_2") (pintype "passive"))
      (node (ref "U1") (pin "73") (pinfunction "VCAP2_73") (pintype "power_in"))
    )
    (net (code "98") (name "Net-(U1C-VSSA)") (class "Default")
      (node (ref "R6") (pin "1") (pinfunction "1_1") (pintype "passive"))
      (node (ref "U1") (pin "19") (pinfunction "VSSA_19") (pintype "power_in"))
    )
    (net (code "99") (name "Net-(VD1-K)") (class "Default")
      (node (ref "R2") (pin "2") (pinfunction "2_2") (pintype "passive"))
      (node (ref "VD1") (pin "2") (pinfunction "K_2") (pintype "passive"))
    )
    (net (code "100") (name "USB_VCC") (class "Default")
      (node (ref "F1") (pin "1") (pinfunction "1_1") (pintype "passive"))
      (node (ref "USB1") (pin "a4") (pinfunction "vbus_a4") (pintype "passive"))
      (node (ref "USB1") (pin "a9") (pinfunction "vbus_a9") (pintype "passive"))
      (node (ref "USB1") (pin "b4") (pinfunction "vbus_b4") (pintype "passive"))
      (node (ref "USB1") (pin "b9") (pinfunction "vbus_b9") (pintype "passive"))
    )
    (net (code "101") (name "VCC") (class "Default")
      (node (ref "C5") (pin "2") (pinfunction "2_2") (pintype "passive"))
      (node (ref "C6") (pin "2") (pinfunction "2_2") (pintype "passive"))
      (node (ref "C7") (pin "2") (pinfunction "2_2") (pintype "passive"))
      (node (ref "CON1") (pin "1") (pintype "power_in"))
      (node (ref "DC") (pin "1") (pinfunction "1_1") (pintype "passive"))
      (node (ref "DC") (pin "4") (pinfunction "4_4") (pintype "passive"))
      (node (ref "DC1") (pin "1") (pinfunction "1_1") (pintype "passive"))
      (node (ref "DC1") (pin "4") (pinfunction "4_4") (pintype "passive"))
      (node (ref "F1") (pin "2") (pinfunction "2_2") (pintype "passive"))
      (node (ref "JP1") (pin "3") (pinfunction "3_3") (pintype "passive"))
      (node (ref "JP1") (pin "4") (pinfunction "4_4") (pintype "passive"))
      (node (ref "JP2") (pin "3") (pinfunction "3_3") (pintype "passive"))
      (node (ref "R8") (pin "2") (pinfunction "2_2") (pintype "passive"))
      (node (ref "R9") (pin "2") (pinfunction "2_2") (pintype "passive"))
      (node (ref "V1") (pin "3") (pinfunction "Vin_3") (pintype "passive"))
      (node (ref "swd") (pin "2") (pinfunction "2_2") (pintype "passive"))
    )
    (net (code "102") (name "unconnected-(R5-Pad1)") (class "Default")
      (node (ref "R5") (pin "1") (pinfunction "1_1") (pintype "passive"))
    )
    (net (code "103") (name "unconnected-(R5-Pad8)") (class "Default")
      (node (ref "R5") (pin "8") (pinfunction "8_8") (pintype "passive"))
    )
    (net (code "104") (name "unconnected-(R7-Pad4)") (class "Default")
      (node (ref "R7") (pin "4") (pinfunction "4_4") (pintype "passive"))
    )
    (net (code "105") (name "unconnected-(R7-Pad5)") (class "Default")
      (node (ref "R7") (pin "5") (pinfunction "5_5") (pintype "passive"))
    )
    (net (code "106") (name "unconnected-(USB1-cc1-Pada5)") (class "Default")
      (node (ref "USB1") (pin "a5") (pinfunction "cc1_a5") (pintype "passive"))
    )
    (net (code "107") (name "unconnected-(USB1-cc2-Padb5)") (class "Default")
      (node (ref "USB1") (pin "b5") (pinfunction "cc2_b5") (pintype "passive"))
    )
    (net (code "108") (name "unconnected-(USB1-rx1+-Padb11)") (class "Default")
      (node (ref "USB1") (pin "b11") (pinfunction "rx1+_b11") (pintype "passive"))
    )
    (net (code "109") (name "unconnected-(USB1-rx1--Padb10)") (class "Default")
      (node (ref "USB1") (pin "b10") (pinfunction "rx1-_b10") (pintype "passive"))
    )
    (net (code "110") (name "unconnected-(USB1-rx2+-Pada11)") (class "Default")
      (node (ref "USB1") (pin "a11") (pinfunction "rx2+_a11") (pintype "passive"))
    )
    (net (code "111") (name "unconnected-(USB1-rx2--Pada10)") (class "Default")
      (node (ref "USB1") (pin "a10") (pinfunction "rx2-_a10") (pintype "passive"))
    )
    (net (code "112") (name "unconnected-(USB1-sbu1-Pada8)") (class "Default")
      (node (ref "USB1") (pin "a8") (pinfunction "sbu1_a8") (pintype "passive"))
    )
    (net (code "113") (name "unconnected-(USB1-sbu2-Padb8)") (class "Default")
      (node (ref "USB1") (pin "b8") (pinfunction "sbu2_b8") (pintype "passive"))
    )
    (net (code "114") (name "unconnected-(USB1-tx1+-Pada2)") (class "Default")
      (node (ref "USB1") (pin "a2") (pinfunction "tx1+_a2") (pintype "passive"))
    )
    (net (code "115") (name "unconnected-(USB1-tx1--Pada3)") (class "Default")
      (node (ref "USB1") (pin "a3") (pinfunction "tx1-_a3") (pintype "passive"))
    )
    (net (code "116") (name "unconnected-(USB1-tx2+-Padb2)") (class "Default")
      (node (ref "USB1") (pin "b2") (pinfunction "tx2+_b2") (pintype "passive"))
    )
    (net (code "117") (name "unconnected-(USB1-tx2--Padb3)") (class "Default")
      (node (ref "USB1") (pin "b3") (pinfunction "tx2-_b3") (pintype "passive"))
    )
    (net (code "118") (name "unconnected-(swd-Pad10)") (class "Default")
      (node (ref "swd") (pin "10") (pinfunction "10_10") (pintype "passive+no_connect"))
    )
  )
)
